# Sheet1.net
KiCad netlist of a schematic drawn in Altium Designer
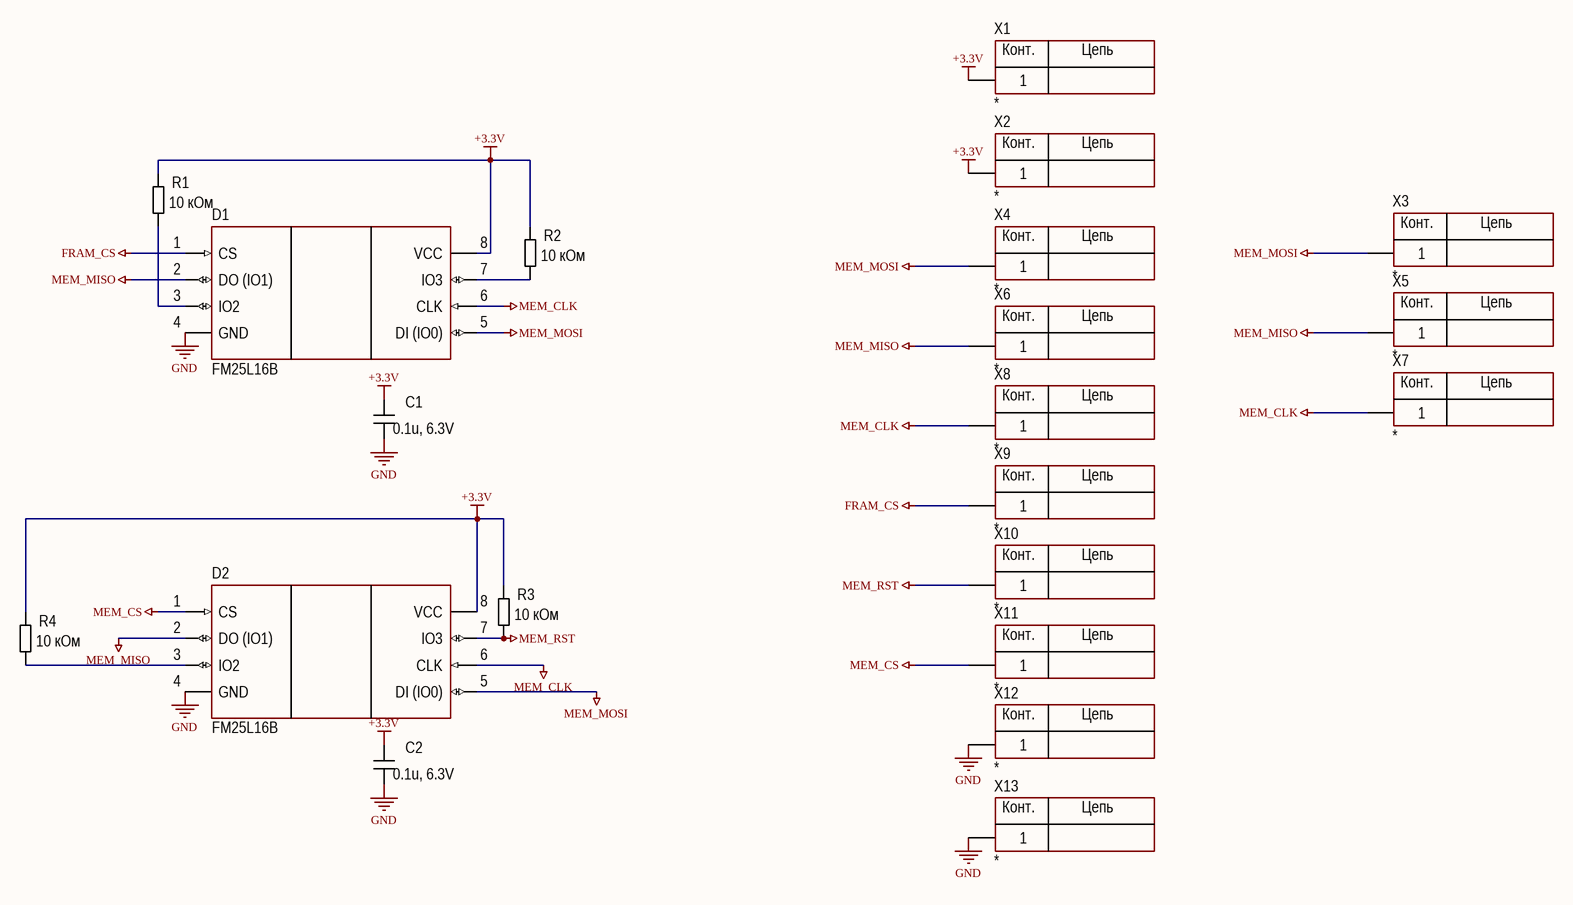
[diagram p0: Sheet1.SchDoc]

(export (version "E")
  (design (tool "Eeschema 10.0.6"))
  (components
    (comp (ref "C1")
      (value "0.1u, 6.3V")
      (footprint "CH0805C")
      (libsource (lib "Condensators") (part "Capacitor"))
    )
    (comp (ref "C2")
      (value "0.1u, 6.3V")
      (footprint "CH0805C")
      (libsource (lib "Condensators") (part "Capacitor"))
    )
    (comp (ref "D1")
      (value "FM25L16B")
      (footprint "8-SOIC")
      (description "Flash")
      (fields (field (name "MANUFACTURER") "Winbond Electronics"))
      (libsource (lib "MicroIC") (part "W25Q80JVSSIQ"))
    )
    (comp (ref "D2")
      (value "FM25L16B")
      (footprint "8-SOIC")
      (description "Flash")
      (fields (field (name "MANUFACTURER") "Winbond Electronics"))
      (libsource (lib "MicroIC") (part "W25Q80JVSSIQ"))
    )
    (comp (ref "R1")
      (value "10 кОм")
      (footprint "CH1206R")
      (description "0603")
      (libsource (lib "Resistors") (part "Resistor"))
    )
    (comp (ref "R2")
      (value "10 кОм")
      (footprint "CH1206R")
      (description "0603")
      (libsource (lib "Resistors") (part "Resistor"))
    )
    (comp (ref "R3")
      (value "10 кОм")
      (footprint "CH1206R")
      (description "0603")
      (libsource (lib "Resistors") (part "Resistor"))
    )
    (comp (ref "R4")
      (value "10 кОм")
      (footprint "CH1206R")
      (description "0603")
      (libsource (lib "Resistors") (part "Resistor"))
    )
    (comp (ref "X1")
      (value "*")
      (footprint "CON: PADS 1x1mm")
      (libsource (lib "Connectors") (part "1-Connector"))
    )
    (comp (ref "X2")
      (value "*")
      (footprint "CON: PADS 1x1mm")
      (libsource (lib "Connectors") (part "1-Connector"))
    )
    (comp (ref "X3")
      (value "*")
      (footprint "CON: PADS 1x1mm")
      (libsource (lib "Connectors") (part "1-Connector"))
    )
    (comp (ref "X4")
      (value "*")
      (footprint "CON: PADS 1x1mm")
      (libsource (lib "Connectors") (part "1-Connector"))
    )
    (comp (ref "X5")
      (value "*")
      (footprint "CON: PADS 1x1mm")
      (libsource (lib "Connectors") (part "1-Connector"))
    )
    (comp (ref "X6")
      (value "*")
      (footprint "CON: PADS 1x1mm")
      (libsource (lib "Connectors") (part "1-Connector"))
    )
    (comp (ref "X7")
      (value "*")
      (footprint "CON: PADS 1x1mm")
      (libsource (lib "Connectors") (part "1-Connector"))
    )
    (comp (ref "X8")
      (value "*")
      (footprint "CON: PADS 1x1mm")
      (libsource (lib "Connectors") (part "1-Connector"))
    )
    (comp (ref "X9")
      (value "*")
      (footprint "CON: PADS 1x1mm")
      (libsource (lib "Connectors") (part "1-Connector"))
    )
    (comp (ref "X10")
      (value "*")
      (footprint "CON: PADS 1x1mm")
      (libsource (lib "Connectors") (part "1-Connector"))
    )
    (comp (ref "X11")
      (value "*")
      (footprint "CON: PADS 1x1mm")
      (libsource (lib "Connectors") (part "1-Connector"))
    )
    (comp (ref "X12")
      (value "*")
      (footprint "CON: PADS 1x1mm")
      (libsource (lib "Connectors") (part "1-Connector"))
    )
    (comp (ref "X13")
      (value "*")
      (footprint "CON: PADS 1x1mm")
      (libsource (lib "Connectors") (part "1-Connector"))
    )
  )
  (nets
    (net (code "1") (name "+3.3V") (class "Default")
      (node (ref "C1") (pin "2") (pinfunction "2_2") (pintype "passive"))
      (node (ref "C2") (pin "2") (pinfunction "2_2") (pintype "passive"))
      (node (ref "D1") (pin "8") (pinfunction "VCC_8") (pintype "power_in"))
      (node (ref "D2") (pin "8") (pinfunction "VCC_8") (pintype "power_in"))
      (node (ref "R1") (pin "2") (pinfunction "2_2") (pintype "passive"))
      (node (ref "R2") (pin "2") (pinfunction "2_2") (pintype "passive"))
      (node (ref "R3") (pin "2") (pinfunction "2_2") (pintype "passive"))
      (node (ref "R4") (pin "2") (pinfunction "2_2") (pintype "passive"))
      (node (ref "X1") (pin "1") (pinfunction "1_1") (pintype "passive"))
      (node (ref "X2") (pin "1") (pinfunction "1_1") (pintype "passive"))
    )
    (net (code "2") (name "FRAM_CS") (class "Default")
      (node (ref "D1") (pin "1") (pinfunction "CS_1") (pintype "input"))
      (node (ref "X9") (pin "1") (pinfunction "1_1") (pintype "passive"))
    )
    (net (code "3") (name "GND") (class "Default")
      (node (ref "C1") (pin "1") (pinfunction "1_1") (pintype "passive"))
      (node (ref "C2") (pin "1") (pinfunction "1_1") (pintype "passive"))
      (node (ref "D1") (pin "4") (pinfunction "GND_4") (pintype "power_in"))
      (node (ref "D2") (pin "4") (pinfunction "GND_4") (pintype "power_in"))
      (node (ref "X12") (pin "1") (pinfunction "1_1") (pintype "passive"))
      (node (ref "X13") (pin "1") (pinfunction "1_1") (pintype "passive"))
    )
    (net (code "4") (name "MEM_CLK") (class "Default")
      (node (ref "D1") (pin "6") (pinfunction "CLK_6") (pintype "input"))
      (node (ref "D2") (pin "6") (pinfunction "CLK_6") (pintype "input"))
      (node (ref "X7") (pin "1") (pinfunction "1_1") (pintype "passive"))
      (node (ref "X8") (pin "1") (pinfunction "1_1") (pintype "passive"))
    )
    (net (code "5") (name "MEM_CS") (class "Default")
      (node (ref "D2") (pin "1") (pinfunction "CS_1") (pintype "input"))
      (node (ref "X11") (pin "1") (pinfunction "1_1") (pintype "passive"))
    )
    (net (code "6") (name "MEM_MISO") (class "Default")
      (node (ref "D1") (pin "2") (pinfunction "DO_(IO1)_2") (pintype "bidirectional"))
      (node (ref "D2") (pin "2") (pinfunction "DO_(IO1)_2") (pintype "bidirectional"))
      (node (ref "X5") (pin "1") (pinfunction "1_1") (pintype "passive"))
      (node (ref "X6") (pin "1") (pinfunction "1_1") (pintype "passive"))
    )
    (net (code "7") (name "MEM_MOSI") (class "Default")
      (node (ref "D1") (pin "5") (pinfunction "DI_(IO0)_5") (pintype "bidirectional"))
      (node (ref "D2") (pin "5") (pinfunction "DI_(IO0)_5") (pintype "bidirectional"))
      (node (ref "X3") (pin "1") (pinfunction "1_1") (pintype "passive"))
      (node (ref "X4") (pin "1") (pinfunction "1_1") (pintype "passive"))
    )
    (net (code "8") (name "MEM_RST") (class "Default")
      (node (ref "D2") (pin "7") (pinfunction "IO3_7") (pintype "bidirectional"))
      (node (ref "R3") (pin "1") (pinfunction "1_1") (pintype "passive"))
      (node (ref "X10") (pin "1") (pinfunction "1_1") (pintype "passive"))
    )
    (net (code "9") (name "Net-(D1-IO2)") (class "Default")
      (node (ref "D1") (pin "3") (pinfunction "IO2_3") (pintype "bidirectional"))
      (node (ref "R1") (pin "1") (pinfunction "1_1") (pintype "passive"))
    )
    (net (code "10") (name "Net-(D1-IO3)") (class "Default")
      (node (ref "D1") (pin "7") (pinfunction "IO3_7") (pintype "bidirectional"))
      (node (ref "R2") (pin "1") (pinfunction "1_1") (pintype "passive"))
    )
    (net (code "11") (name "Net-(D2-IO2)") (class "Default")
      (node (ref "D2") (pin "3") (pinfunction "IO2_3") (pintype "bidirectional"))
      (node (ref "R4") (pin "1") (pinfunction "1_1") (pintype "passive"))
    )
  )
)
